# ADC_1.net
KiCad netlist of a schematic drawn in Altium Designer
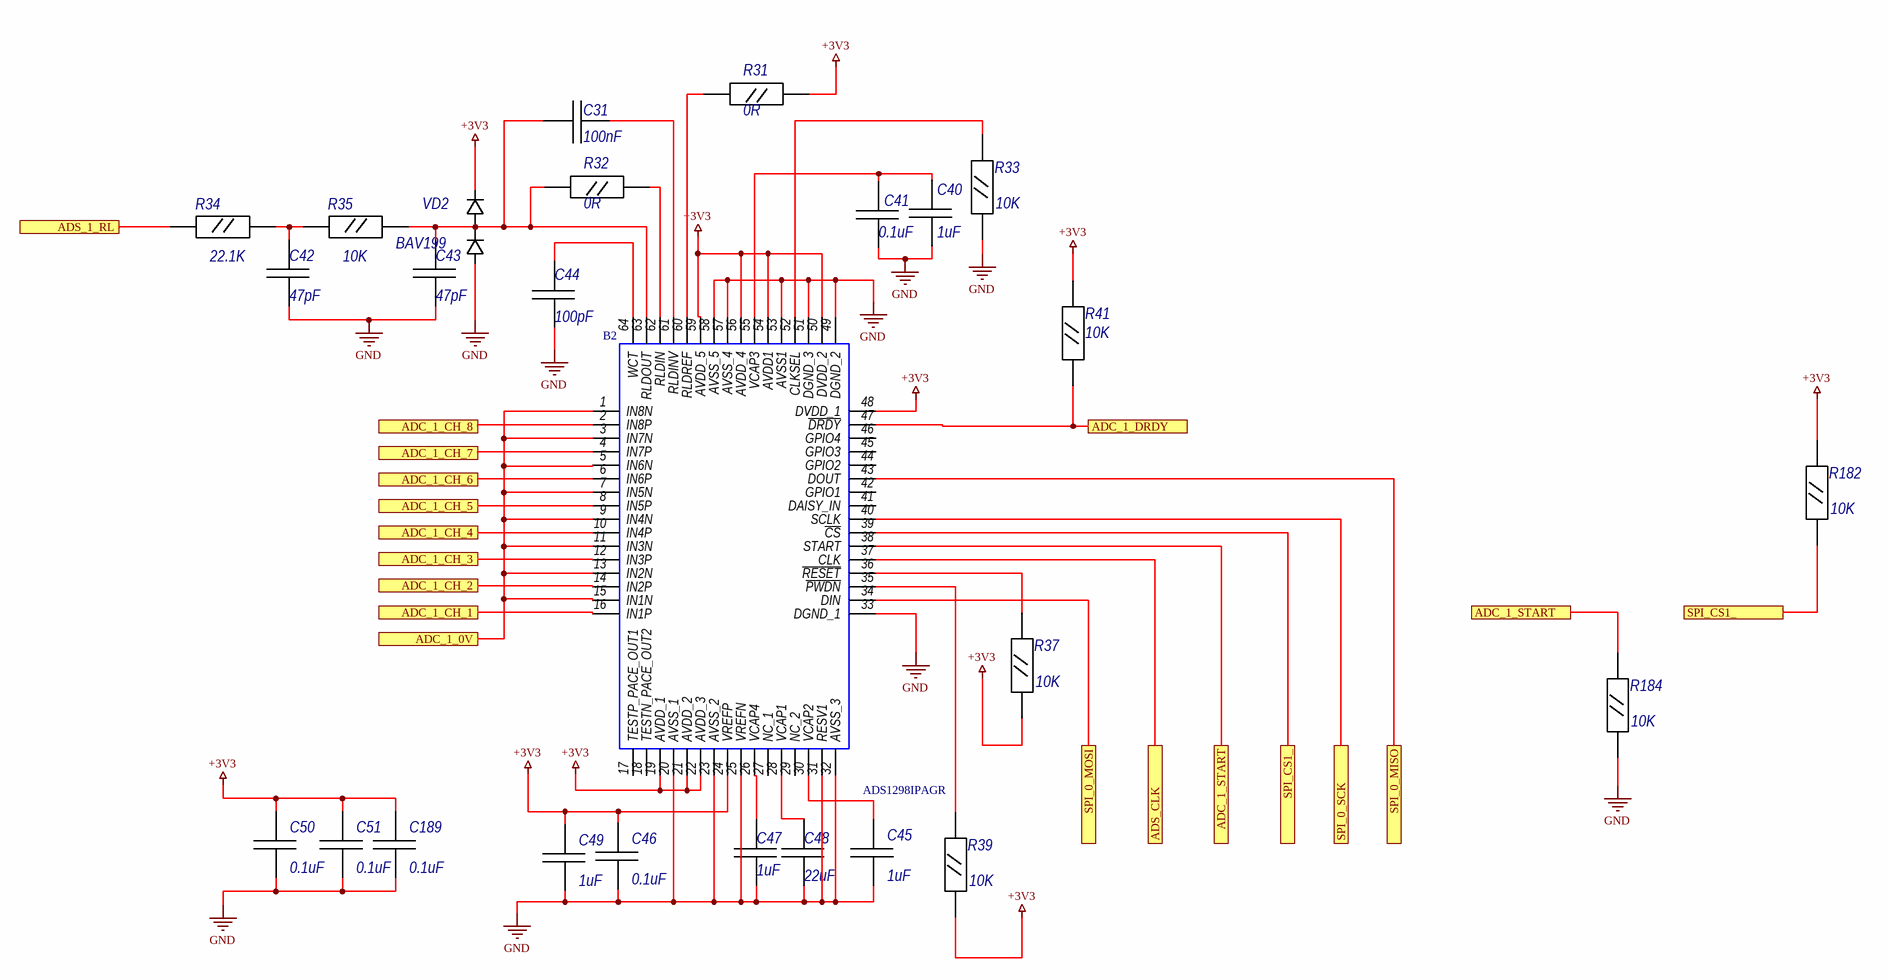
[diagram p0: ADC_1.SchDoc]

(export (version "E")
  (design (tool "Eeschema 10.0.6"))
  (components
    (comp (ref "B2")
      (value "ADS1298IPAGR")
      (footprint "QFP50P1200X1200X120-64N")
      (description "8-Channel 24-bit ADC With Integrated ECG Front End")
      (fields (field (name "MOUSER PART NUMBER") "595-ADS1298IPAGR"))
      (libsource (lib "ADS1298IPAGR") (part "ADS1298IPAGR"))
    )
    (comp (ref "C31")
      (value "100nF")
      (footprint "C0603")
      (description "Ceramic Capacitor SMD")
      (libsource (lib "GOST") (part "CC_SMD_0603"))
    )
    (comp (ref "C40")
      (value "1uF")
      (footprint "C0603")
      (description "Ceramic Capacitor SMD")
      (libsource (lib "GOST") (part "CC_SMD_0603"))
    )
    (comp (ref "C41")
      (value "0.1uF")
      (footprint "C0603")
      (description "Ceramic Capacitor SMD")
      (libsource (lib "GOST") (part "CC_SMD_0603"))
    )
    (comp (ref "C42")
      (value "47pF")
      (footprint "C0603")
      (description "Ceramic Capacitor SMD")
      (libsource (lib "GOST") (part "CC_SMD_0603"))
    )
    (comp (ref "C43")
      (value "47pF")
      (footprint "C0603")
      (description "Ceramic Capacitor SMD")
      (libsource (lib "GOST") (part "CC_SMD_0603"))
    )
    (comp (ref "C44")
      (value "100pF")
      (footprint "C0603")
      (description "Ceramic Capacitor SMD")
      (libsource (lib "GOST") (part "CC_SMD_0603"))
    )
    (comp (ref "C45")
      (value "1uF")
      (footprint "C0603")
      (description "Ceramic Capacitor SMD")
      (libsource (lib "GOST") (part "CC_SMD_0603"))
    )
    (comp (ref "C46")
      (value "0.1uF")
      (footprint "C0603")
      (description "Ceramic Capacitor SMD")
      (libsource (lib "GOST") (part "CC_SMD_0603"))
    )
    (comp (ref "C47")
      (value "1uF")
      (footprint "C0603")
      (description "Ceramic Capacitor SMD")
      (libsource (lib "GOST") (part "CC_SMD_0603"))
    )
    (comp (ref "C48")
      (value "22uF")
      (footprint "C0603")
      (description "Ceramic Capacitor SMD")
      (libsource (lib "GOST") (part "CC_SMD_0603"))
    )
    (comp (ref "C49")
      (value "1uF")
      (footprint "C0603")
      (description "Ceramic Capacitor SMD")
      (libsource (lib "GOST") (part "CC_SMD_0603"))
    )
    (comp (ref "C50")
      (value "0.1uF")
      (footprint "C0603")
      (description "Ceramic Capacitor SMD")
      (libsource (lib "GOST") (part "CC_SMD_0603"))
    )
    (comp (ref "C51")
      (value "0.1uF")
      (footprint "C0603")
      (description "Ceramic Capacitor SMD")
      (libsource (lib "GOST") (part "CC_SMD_0603"))
    )
    (comp (ref "C189")
      (value "0.1uF")
      (footprint "C0603")
      (description "Ceramic Capacitor SMD")
      (libsource (lib "GOST") (part "CC_SMD_0603"))
    )
    (comp (ref "R31")
      (value "0R")
      (footprint "R0603")
      (description "Resistor SMD")
      (libsource (lib "GOST") (part "R0603"))
    )
    (comp (ref "R32")
      (value "0R")
      (footprint "R0603")
      (description "Resistor SMD")
      (libsource (lib "GOST") (part "R0603"))
    )
    (comp (ref "R33")
      (value "10K")
      (footprint "R0603")
      (description "Resistor SMD")
      (libsource (lib "GOST") (part "R0603"))
    )
    (comp (ref "R34")
      (value "22.1K")
      (footprint "R0603")
      (description "Resistor SMD")
      (libsource (lib "GOST") (part "R0603"))
    )
    (comp (ref "R35")
      (value "10K")
      (footprint "R0603")
      (description "Resistor SMD")
      (libsource (lib "GOST") (part "R0603"))
    )
    (comp (ref "R37")
      (value "10K")
      (footprint "R0603")
      (description "Resistor SMD")
      (libsource (lib "GOST") (part "R0603"))
    )
    (comp (ref "R39")
      (value "10K")
      (footprint "R0603")
      (description "Resistor SMD")
      (libsource (lib "GOST") (part "R0603"))
    )
    (comp (ref "R41")
      (value "10K")
      (footprint "R0603")
      (description "Resistor SMD")
      (libsource (lib "GOST") (part "R0603"))
    )
    (comp (ref "R182")
      (value "10K")
      (footprint "R0603")
      (description "Resistor SMD")
      (libsource (lib "GOST") (part "R0603"))
    )
    (comp (ref "R184")
      (value "10K")
      (footprint "R0603")
      (description "Resistor SMD")
      (libsource (lib "GOST") (part "R0603"))
    )
    (comp (ref "VD2")
      (value "BAV199")
      (footprint "SOT23")
      (description "Diod Schottky")
      (fields (field (name "MANUFACTURER PART NUMBER 1") "BAV199"))
      (libsource (lib "GOST") (part "DIODE_BAV199"))
    )
  )
  (nets
    (net (code "1") (name "+3V3") (class "Default")
      (node (ref "B2") (pin "19") (pinfunction "AVDD_1_19") (pintype "passive"))
      (node (ref "B2") (pin "21") (pinfunction "AVDD_2_21") (pintype "passive"))
      (node (ref "B2") (pin "22") (pinfunction "AVDD_3_22") (pintype "passive"))
      (node (ref "B2") (pin "24") (pinfunction "VREFP_24") (pintype "passive"))
      (node (ref "B2") (pin "48") (pinfunction "DVDD_1_48") (pintype "passive"))
      (node (ref "B2") (pin "50") (pinfunction "DVDD_2_50") (pintype "passive"))
      (node (ref "B2") (pin "54") (pinfunction "AVDD1_54") (pintype "passive"))
      (node (ref "B2") (pin "56") (pinfunction "AVDD_4_56") (pintype "passive"))
      (node (ref "B2") (pin "59") (pinfunction "AVDD_5_59") (pintype "passive"))
      (node (ref "C189") (pin "2") (pinfunction "2_2") (pintype "passive"))
      (node (ref "C46") (pin "2") (pinfunction "2_2") (pintype "passive"))
      (node (ref "C49") (pin "2") (pinfunction "2_2") (pintype "passive"))
      (node (ref "C50") (pin "2") (pinfunction "2_2") (pintype "passive"))
      (node (ref "C51") (pin "2") (pinfunction "2_2") (pintype "passive"))
      (node (ref "R182") (pin "2") (pinfunction "2_2") (pintype "passive"))
      (node (ref "R31") (pin "1") (pinfunction "1_1") (pintype "passive"))
      (node (ref "R37") (pin "1") (pinfunction "1_1") (pintype "passive"))
      (node (ref "R39") (pin "1") (pinfunction "1_1") (pintype "passive"))
      (node (ref "R41") (pin "2") (pinfunction "2_2") (pintype "passive"))
      (node (ref "VD2") (pin "2") (pinfunction "2_2") (pintype "passive"))
    )
    (net (code "2") (name "/ADC_1_0V") (class "Default")
      (node (ref "B2") (pin "1") (pinfunction "IN8N_1") (pintype "passive"))
      (node (ref "B2") (pin "11") (pinfunction "IN3N_11") (pintype "passive"))
      (node (ref "B2") (pin "13") (pinfunction "IN2N_13") (pintype "passive"))
      (node (ref "B2") (pin "15") (pinfunction "IN1N_15") (pintype "passive"))
      (node (ref "B2") (pin "3") (pinfunction "IN7N_3") (pintype "passive"))
      (node (ref "B2") (pin "5") (pinfunction "IN6N_5") (pintype "passive"))
      (node (ref "B2") (pin "7") (pinfunction "IN5N_7") (pintype "passive"))
      (node (ref "B2") (pin "9") (pinfunction "IN4N_9") (pintype "passive"))
    )
    (net (code "3") (name "/ADC_1_CH_1") (class "Default")
      (node (ref "B2") (pin "16") (pinfunction "IN1P_16") (pintype "passive"))
    )
    (net (code "4") (name "/ADC_1_CH_2") (class "Default")
      (node (ref "B2") (pin "14") (pinfunction "IN2P_14") (pintype "passive"))
    )
    (net (code "5") (name "/ADC_1_CH_3") (class "Default")
      (node (ref "B2") (pin "12") (pinfunction "IN3P_12") (pintype "passive"))
    )
    (net (code "6") (name "/ADC_1_CH_4") (class "Default")
      (node (ref "B2") (pin "10") (pinfunction "IN4P_10") (pintype "passive"))
    )
    (net (code "7") (name "/ADC_1_CH_5") (class "Default")
      (node (ref "B2") (pin "8") (pinfunction "IN5P_8") (pintype "passive"))
    )
    (net (code "8") (name "/ADC_1_CH_6") (class "Default")
      (node (ref "B2") (pin "6") (pinfunction "IN6P_6") (pintype "passive"))
    )
    (net (code "9") (name "/ADC_1_CH_7") (class "Default")
      (node (ref "B2") (pin "4") (pinfunction "IN7P_4") (pintype "passive"))
    )
    (net (code "10") (name "/ADC_1_CH_8") (class "Default")
      (node (ref "B2") (pin "2") (pinfunction "IN8P_2") (pintype "passive"))
    )
    (net (code "11") (name "/ADC_1_DRDY") (class "Default")
      (node (ref "B2") (pin "47") (pinfunction "DRDY_47") (pintype "passive"))
      (node (ref "R41") (pin "1") (pinfunction "1_1") (pintype "passive"))
    )
    (net (code "12") (name "/ADC_1_START") (class "Default")
      (node (ref "B2") (pin "38") (pinfunction "START_38") (pintype "passive"))
      (node (ref "R184") (pin "2") (pinfunction "2_2") (pintype "passive"))
    )
    (net (code "13") (name "/ADS_1_RL") (class "Default")
      (node (ref "R34") (pin "1") (pinfunction "1_1") (pintype "passive"))
    )
    (net (code "14") (name "/ADS_CLK") (class "Default")
      (node (ref "B2") (pin "37") (pinfunction "CLK_37") (pintype "passive"))
    )
    (net (code "15") (name "/SPI_0_MISO") (class "Default")
      (node (ref "B2") (pin "43") (pinfunction "DOUT_43") (pintype "passive"))
    )
    (net (code "16") (name "/SPI_0_MOSI") (class "Default")
      (node (ref "B2") (pin "34") (pinfunction "DIN_34") (pintype "passive"))
    )
    (net (code "17") (name "/SPI_0_SCK") (class "Default")
      (node (ref "B2") (pin "40") (pinfunction "SCLK_40") (pintype "passive"))
    )
    (net (code "18") (name "/SPI_CS1_") (class "Default")
      (node (ref "B2") (pin "39") (pinfunction "CS_39") (pintype "passive"))
      (node (ref "R182") (pin "1") (pinfunction "1_1") (pintype "passive"))
    )
    (net (code "19") (name "GND") (class "Default")
      (node (ref "B2") (pin "20") (pinfunction "AVSS_1_20") (pintype "passive"))
      (node (ref "B2") (pin "23") (pinfunction "AVSS_2_23") (pintype "passive"))
      (node (ref "B2") (pin "25") (pinfunction "VREFN_25") (pintype "passive"))
      (node (ref "B2") (pin "31") (pinfunction "RESV1_31") (pintype "passive"))
      (node (ref "B2") (pin "32") (pinfunction "AVSS_3_32") (pintype "passive"))
      (node (ref "B2") (pin "33") (pinfunction "DGND_1_33") (pintype "passive"))
      (node (ref "B2") (pin "49") (pinfunction "DGND_2_49") (pintype "passive"))
      (node (ref "B2") (pin "51") (pinfunction "DGND_3_51") (pintype "passive"))
      (node (ref "B2") (pin "53") (pinfunction "AVSS1_53") (pintype "passive"))
      (node (ref "B2") (pin "57") (pinfunction "AVSS_4_57") (pintype "passive"))
      (node (ref "B2") (pin "58") (pinfunction "AVSS_5_58") (pintype "passive"))
      (node (ref "C189") (pin "1") (pinfunction "1_1") (pintype "passive"))
      (node (ref "C40") (pin "1") (pinfunction "1_1") (pintype "passive"))
      (node (ref "C41") (pin "1") (pinfunction "1_1") (pintype "passive"))
      (node (ref "C42") (pin "1") (pinfunction "1_1") (pintype "passive"))
      (node (ref "C43") (pin "1") (pinfunction "1_1") (pintype "passive"))
      (node (ref "C44") (pin "1") (pinfunction "1_1") (pintype "passive"))
      (node (ref "C45") (pin "1") (pinfunction "1_1") (pintype "passive"))
      (node (ref "C46") (pin "1") (pinfunction "1_1") (pintype "passive"))
      (node (ref "C47") (pin "1") (pinfunction "1_1") (pintype "passive"))
      (node (ref "C48") (pin "1") (pinfunction "1_1") (pintype "passive"))
      (node (ref "C49") (pin "1") (pinfunction "1_1") (pintype "passive"))
      (node (ref "C50") (pin "1") (pinfunction "1_1") (pintype "passive"))
      (node (ref "C51") (pin "1") (pinfunction "1_1") (pintype "passive"))
      (node (ref "R184") (pin "1") (pinfunction "1_1") (pintype "passive"))
      (node (ref "R33") (pin "1") (pinfunction "1_1") (pintype "passive"))
      (node (ref "VD2") (pin "1") (pinfunction "1_1") (pintype "passive"))
    )
    (net (code "20") (name "Net-(B2-CLKSEL)") (class "Default")
      (node (ref "B2") (pin "52") (pinfunction "CLKSEL_52") (pintype "passive"))
      (node (ref "R33") (pin "2") (pinfunction "2_2") (pintype "passive"))
    )
    (net (code "21") (name "Net-(B2-PWDN)") (class "Default")
      (node (ref "B2") (pin "35") (pinfunction "PWDN_35") (pintype "passive"))
      (node (ref "R39") (pin "2") (pinfunction "2_2") (pintype "passive"))
    )
    (net (code "22") (name "Net-(B2-RESET)") (class "Default")
      (node (ref "B2") (pin "36") (pinfunction "RESET_36") (pintype "passive"))
      (node (ref "R37") (pin "2") (pinfunction "2_2") (pintype "passive"))
    )
    (net (code "23") (name "Net-(B2-RLDIN)") (class "Default")
      (node (ref "B2") (pin "62") (pinfunction "RLDIN_62") (pintype "passive"))
      (node (ref "R32") (pin "1") (pinfunction "1_1") (pintype "passive"))
    )
    (net (code "24") (name "Net-(B2-RLDINV)") (class "Default")
      (node (ref "B2") (pin "61") (pinfunction "RLDINV_61") (pintype "passive"))
      (node (ref "C31") (pin "1") (pinfunction "1_1") (pintype "passive"))
    )
    (net (code "25") (name "Net-(B2-RLDOUT)") (class "Default")
      (node (ref "B2") (pin "63") (pinfunction "RLDOUT_63") (pintype "passive"))
      (node (ref "C31") (pin "2") (pinfunction "2_2") (pintype "passive"))
      (node (ref "C43") (pin "2") (pinfunction "2_2") (pintype "passive"))
      (node (ref "R32") (pin "2") (pinfunction "2_2") (pintype "passive"))
      (node (ref "R35") (pin "2") (pinfunction "2_2") (pintype "passive"))
      (node (ref "VD2") (pin "3") (pinfunction "3_3") (pintype "passive"))
    )
    (net (code "26") (name "Net-(B2-RLDREF)") (class "Default")
      (node (ref "B2") (pin "60") (pinfunction "RLDREF_60") (pintype "passive"))
      (node (ref "R31") (pin "2") (pinfunction "2_2") (pintype "passive"))
    )
    (net (code "27") (name "Net-(B2-VCAP1)") (class "Default")
      (node (ref "B2") (pin "28") (pinfunction "VCAP1_28") (pintype "passive"))
      (node (ref "C48") (pin "2") (pinfunction "2_2") (pintype "passive"))
    )
    (net (code "28") (name "Net-(B2-VCAP2)") (class "Default")
      (node (ref "B2") (pin "30") (pinfunction "VCAP2_30") (pintype "passive"))
      (node (ref "C45") (pin "2") (pinfunction "2_2") (pintype "passive"))
    )
    (net (code "29") (name "Net-(B2-VCAP3)") (class "Default")
      (node (ref "B2") (pin "55") (pinfunction "VCAP3_55") (pintype "passive"))
      (node (ref "C40") (pin "2") (pinfunction "2_2") (pintype "passive"))
      (node (ref "C41") (pin "2") (pinfunction "2_2") (pintype "passive"))
    )
    (net (code "30") (name "Net-(B2-VCAP4)") (class "Default")
      (node (ref "B2") (pin "26") (pinfunction "VCAP4_26") (pintype "passive"))
      (node (ref "C47") (pin "2") (pinfunction "2_2") (pintype "passive"))
    )
    (net (code "31") (name "Net-(B2-WCT)") (class "Default")
      (node (ref "B2") (pin "64") (pinfunction "WCT_64") (pintype "passive"))
      (node (ref "C44") (pin "2") (pinfunction "2_2") (pintype "passive"))
    )
    (net (code "32") (name "Net-(C42-Pad2)") (class "Default")
      (node (ref "C42") (pin "2") (pinfunction "2_2") (pintype "passive"))
      (node (ref "R34") (pin "2") (pinfunction "2_2") (pintype "passive"))
      (node (ref "R35") (pin "1") (pinfunction "1_1") (pintype "passive"))
    )
    (net (code "33") (name "unconnected-(B2-DAISY_IN-Pad41)") (class "Default")
      (node (ref "B2") (pin "41") (pinfunction "DAISY_IN_41") (pintype "passive"))
    )
    (net (code "34") (name "unconnected-(B2-GPIO1-Pad42)") (class "Default")
      (node (ref "B2") (pin "42") (pinfunction "GPIO1_42") (pintype "passive"))
    )
    (net (code "35") (name "unconnected-(B2-GPIO2-Pad44)") (class "Default")
      (node (ref "B2") (pin "44") (pinfunction "GPIO2_44") (pintype "passive"))
    )
    (net (code "36") (name "unconnected-(B2-GPIO3-Pad45)") (class "Default")
      (node (ref "B2") (pin "45") (pinfunction "GPIO3_45") (pintype "passive"))
    )
    (net (code "37") (name "unconnected-(B2-GPIO4-Pad46)") (class "Default")
      (node (ref "B2") (pin "46") (pinfunction "GPIO4_46") (pintype "passive"))
    )
    (net (code "38") (name "unconnected-(B2-NC_1-Pad27)") (class "Default")
      (node (ref "B2") (pin "27") (pinfunction "NC_1_27") (pintype "passive"))
    )
    (net (code "39") (name "unconnected-(B2-NC_2-Pad29)") (class "Default")
      (node (ref "B2") (pin "29") (pinfunction "NC_2_29") (pintype "passive"))
    )
    (net (code "40") (name "unconnected-(B2-TESTN_PACE_OUT2-Pad18)") (class "Default")
      (node (ref "B2") (pin "18") (pinfunction "TESTN_PACE_OUT2_18") (pintype "passive"))
    )
    (net (code "41") (name "unconnected-(B2-TESTP_PACE_OUT1-Pad17)") (class "Default")
      (node (ref "B2") (pin "17") (pinfunction "TESTP_PACE_OUT1_17") (pintype "passive"))
    )
  )
)
